# EDU_High-Speed-Design_CPU_Ethernet.net
KiCad netlist of a schematic drawn in Altium Designer
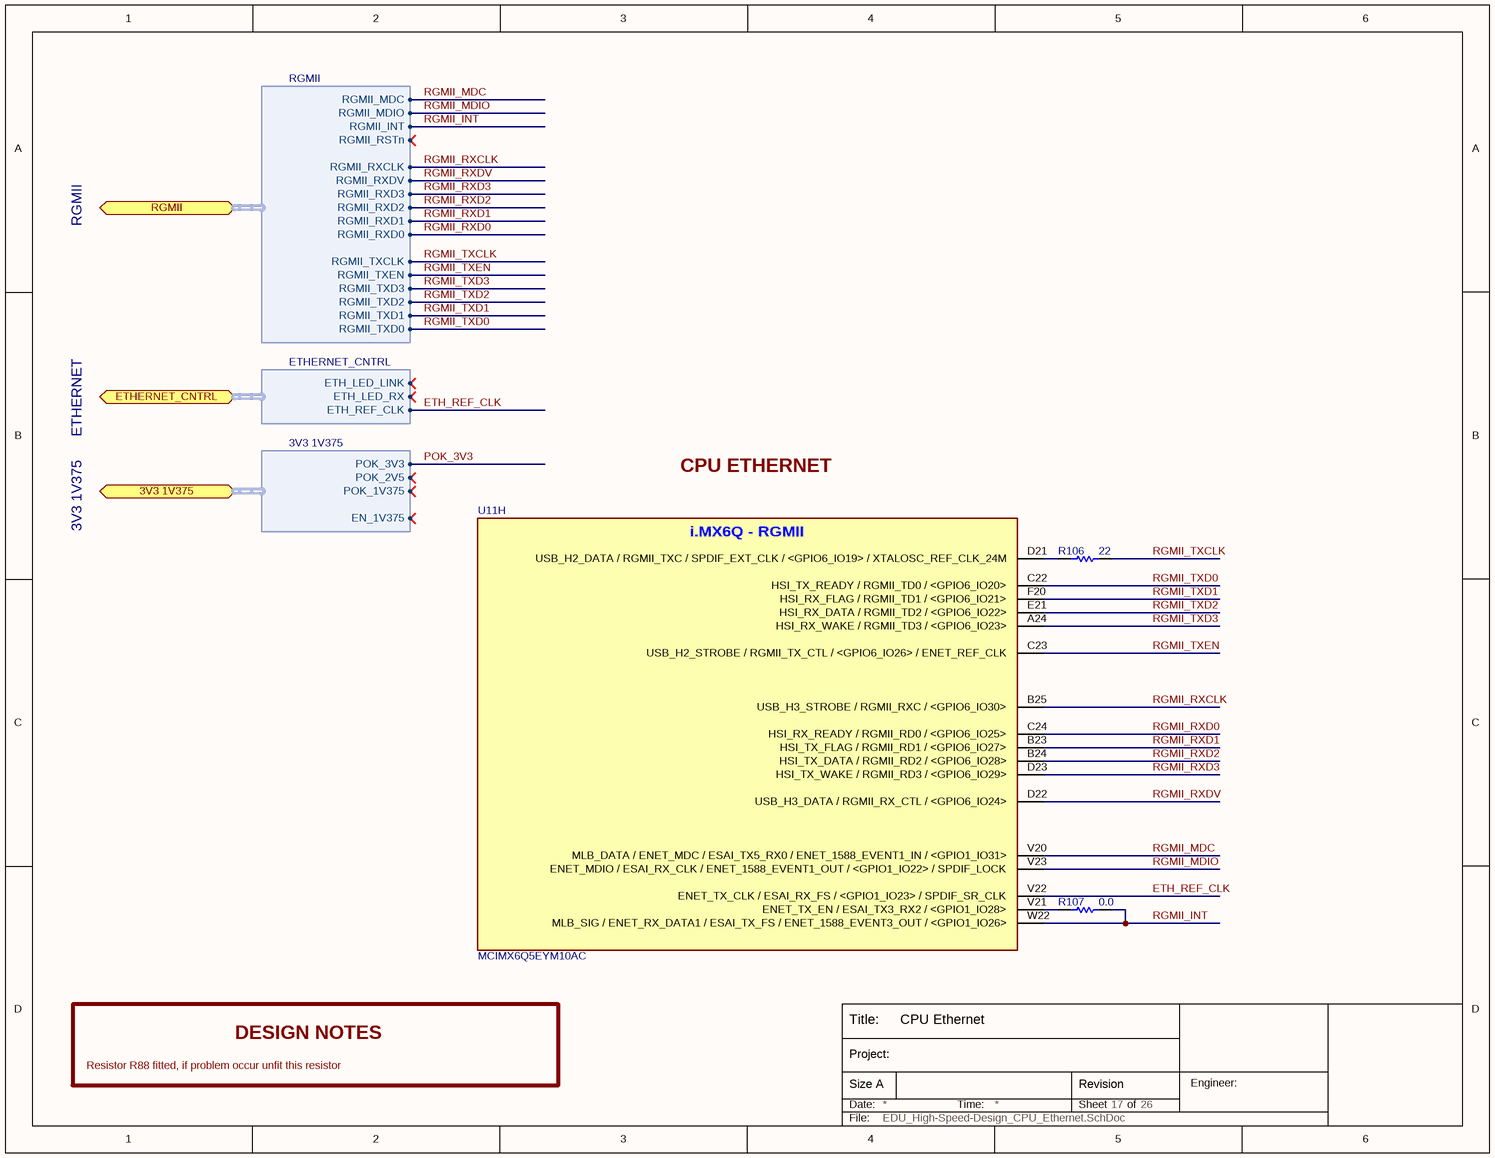
[diagram p0: EDU_High-Speed-Design_CPU_Ethernet.SchDoc]

(export (version "E")
  (design (tool "Eeschema 10.0.6"))
  (components
    (comp (ref "R106")
      (value "22")
      (footprint "R0402")
      (description "RES 22.0 OHM 1/16W 1% 0402 SMD")
      (libsource (lib "EDU_High-Speed-Design") (part "RC0402FR-0722RL"))
    )
    (comp (ref "R107")
      (value "0.0")
      (footprint "R0402")
      (description "RES 0.0 OHM 1/16W 0402 SMD")
      (libsource (lib "EDU_High-Speed-Design") (part "RC0402JR-070RL"))
    )
    (comp (ref "U11")
      (value "MCIMX6Q5EYM10AC")
      (footprint "MCIMX6Q5EYM10AC")
      (description "IC MCU 32BIT ARM QUAD 624FCBGA")
      (libsource (lib "EDU_High-Speed-Design") (part "MCIMX6Q5EYM10AC"))
    )
  )
  (nets
    (net (code "5") (name "/ETH_REF_CLK") (class "Default")
      (node (ref "U11") (pin "V22") (pinfunction "ENET_TX_CLK_/_ESAI_RX_FS_/_<GPIO1_IO23>_/_SPDIF_SR_CLK_V22") (pintype "passive"))
    )
    (net (code "7") (name "/RGMII_INT") (class "Default")
      (node (ref "R107") (pin "1") (pinfunction "1_1") (pintype "passive"))
      (node (ref "U11") (pin "W22") (pinfunction "MLB_SIG_/_ENET_RX_DATA1_/_ESAI_TX_FS_/_ENET_1588_EVENT3_OUT_/_<GPIO1_IO26>_W22") (pintype "passive"))
    )
    (net (code "8") (name "/RGMII_MDC") (class "Default")
      (node (ref "U11") (pin "V20") (pinfunction "MLB_DATA_/_ENET_MDC_/_ESAI_TX5_RX0_/_ENET_1588_EVENT1_IN_/_<GPIO1_IO31>_V20") (pintype "passive"))
    )
    (net (code "9") (name "/RGMII_MDIO") (class "Default")
      (node (ref "U11") (pin "V23") (pinfunction "ENET_MDIO_/_ESAI_RX_CLK_/_ENET_1588_EVENT1_OUT_/_<GPIO1_IO22>_/_SPDIF_LOCK_V23") (pintype "passive"))
    )
    (net (code "10") (name "/RGMII_RXCLK") (class "Default")
      (node (ref "U11") (pin "B25") (pinfunction "USB_H3_STROBE_/_RGMII_RXC_/_<GPIO6_IO30>_B25") (pintype "passive"))
    )
    (net (code "11") (name "/RGMII_RXD0") (class "Default")
      (node (ref "U11") (pin "C24") (pinfunction "HSI_RX_READY_/_RGMII_RD0_/_<GPIO6_IO25>_C24") (pintype "passive"))
    )
    (net (code "12") (name "/RGMII_RXD1") (class "Default")
      (node (ref "U11") (pin "B23") (pinfunction "HSI_TX_FLAG_/_RGMII_RD1_/_<GPIO6_IO27>_B23") (pintype "passive"))
    )
    (net (code "13") (name "/RGMII_RXD2") (class "Default")
      (node (ref "U11") (pin "B24") (pinfunction "HSI_TX_DATA_/_RGMII_RD2_/_<GPIO6_IO28>_B24") (pintype "passive"))
    )
    (net (code "14") (name "/RGMII_RXD3") (class "Default")
      (node (ref "U11") (pin "D23") (pinfunction "HSI_TX_WAKE_/_RGMII_RD3_/_<GPIO6_IO29>_D23") (pintype "passive"))
    )
    (net (code "15") (name "/RGMII_RXDV") (class "Default")
      (node (ref "U11") (pin "D22") (pinfunction "USB_H3_DATA_/_RGMII_RX_CTL_/_<GPIO6_IO24>_D22") (pintype "passive"))
    )
    (net (code "16") (name "/RGMII_TXCLK") (class "Default")
      (node (ref "R106") (pin "1") (pinfunction "1_1") (pintype "passive"))
    )
    (net (code "17") (name "/RGMII_TXD0") (class "Default")
      (node (ref "U11") (pin "C22") (pinfunction "HSI_TX_READY_/_RGMII_TD0_/_<GPIO6_IO20>_C22") (pintype "passive"))
    )
    (net (code "18") (name "/RGMII_TXD1") (class "Default")
      (node (ref "U11") (pin "F20") (pinfunction "HSI_RX_FLAG_/_RGMII_TD1_/_<GPIO6_IO21>_F20") (pintype "passive"))
    )
    (net (code "19") (name "/RGMII_TXD2") (class "Default")
      (node (ref "U11") (pin "E21") (pinfunction "HSI_RX_DATA_/_RGMII_TD2_/_<GPIO6_IO22>_E21") (pintype "passive"))
    )
    (net (code "20") (name "/RGMII_TXD3") (class "Default")
      (node (ref "U11") (pin "A24") (pinfunction "HSI_RX_WAKE_/_RGMII_TD3_/_<GPIO6_IO23>_A24") (pintype "passive"))
    )
    (net (code "21") (name "/RGMII_TXEN") (class "Default")
      (node (ref "U11") (pin "C23") (pinfunction "USB_H2_STROBE_/_RGMII_TX_CTL_/_<GPIO6_IO26>_/_ENET_REF_CLK_C23") (pintype "passive"))
    )
    (net (code "25") (name "Net-(U11H-ENET_TX_EN_{slash}_ESAI_TX3_RX2_{slash}_<GPIO1_IO28>)") (class "Default")
      (node (ref "R107") (pin "2") (pinfunction "2_2") (pintype "passive"))
      (node (ref "U11") (pin "V21") (pinfunction "ENET_TX_EN_/_ESAI_TX3_RX2_/_<GPIO1_IO28>_V21") (pintype "passive"))
    )
    (net (code "26") (name "Net-(U11H-USB_H2_DATA_{slash}_RGMII_TXC_{slash}_SPDIF_EXT_CLK_{slash}_<GPIO6_IO19>_{slash}_XTALOSC_REF_CLK_24M)") (class "Default")
      (node (ref "R106") (pin "2") (pinfunction "2_2") (pintype "passive"))
      (node (ref "U11") (pin "D21") (pinfunction "USB_H2_DATA_/_RGMII_TXC_/_SPDIF_EXT_CLK_/_<GPIO6_IO19>_/_XTALOSC_REF_CLK_24M_D21") (pintype "passive"))
    )
  )
)
